# battery_monitor.net
KiCad netlist of a schematic drawn in Altium Designer
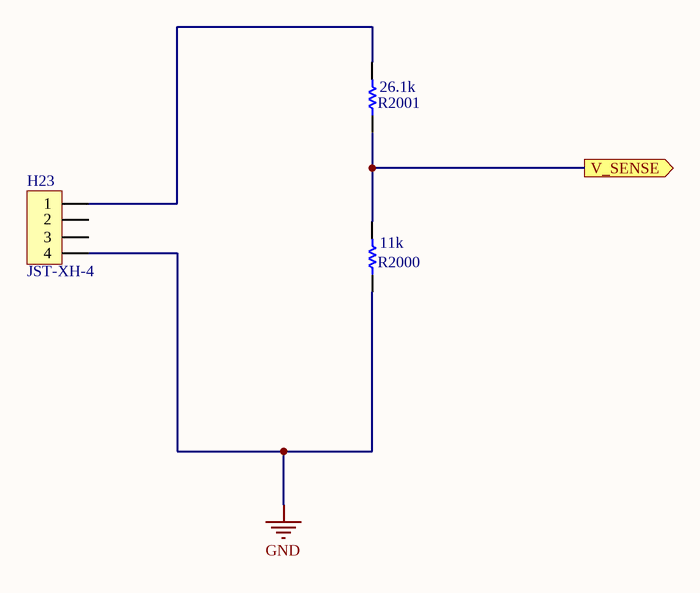
[diagram p0: battery_monitor.SchDoc]

(export (version "E")
  (design (tool "Eeschema 10.0.6"))
  (components
    (comp (ref "H23")
      (value "JST-XH-4")
      (footprint "JST-XH-4")
      (libsource (lib "elevate_lib") (part "JST-XH-4"))
    )
    (comp (ref "R2000")
      (value "11k")
      (footprint "RESC0805(2012)_M")
      (description "11K 0.125W 1% 0805 (2012 Metric)  SMD")
      (fields (field (name "TOLERANCE") "1 %") (field (name "POWER") "0.125 W"))
      (libsource (lib "Altium Content Vault") (part "CMP-1013-00627-1"))
    )
    (comp (ref "R2001")
      (value "26.1k")
      (footprint "RESC0805(2012)_N")
      (description "26K1 0.125W 1% 0805 (2012 Metric)  SMD")
      (fields (field (name "TOLERANCE") "1 %") (field (name "POWER") "0.125 W"))
      (libsource (lib "Altium Content Vault") (part "CMP-1013-00668-1"))
    )
  )
  (nets
    (net (code "1") (name "/V_SENSE") (class "Default")
      (node (ref "R2000") (pin "2") (pinfunction "2_2") (pintype "passive"))
      (node (ref "R2001") (pin "1") (pinfunction "1_1") (pintype "passive"))
    )
    (net (code "2") (name "GND") (class "Default")
      (node (ref "H23") (pin "4") (pinfunction "4_4") (pintype "passive"))
      (node (ref "R2000") (pin "1") (pinfunction "1_1") (pintype "passive"))
    )
    (net (code "3") (name "Net-(H23-Pad1)") (class "Default")
      (node (ref "H23") (pin "1") (pinfunction "1_1") (pintype "passive"))
      (node (ref "R2001") (pin "2") (pinfunction "2_2") (pintype "passive"))
    )
    (net (code "4") (name "unconnected-(H23-Pad2)") (class "Default")
      (node (ref "H23") (pin "2") (pinfunction "2_2") (pintype "passive"))
    )
    (net (code "5") (name "unconnected-(H23-Pad3)") (class "Default")
      (node (ref "H23") (pin "3") (pinfunction "3_3") (pintype "passive"))
    )
  )
)
